# M837-pld-84.net
KiCad netlist of a schematic drawn in EAGLE
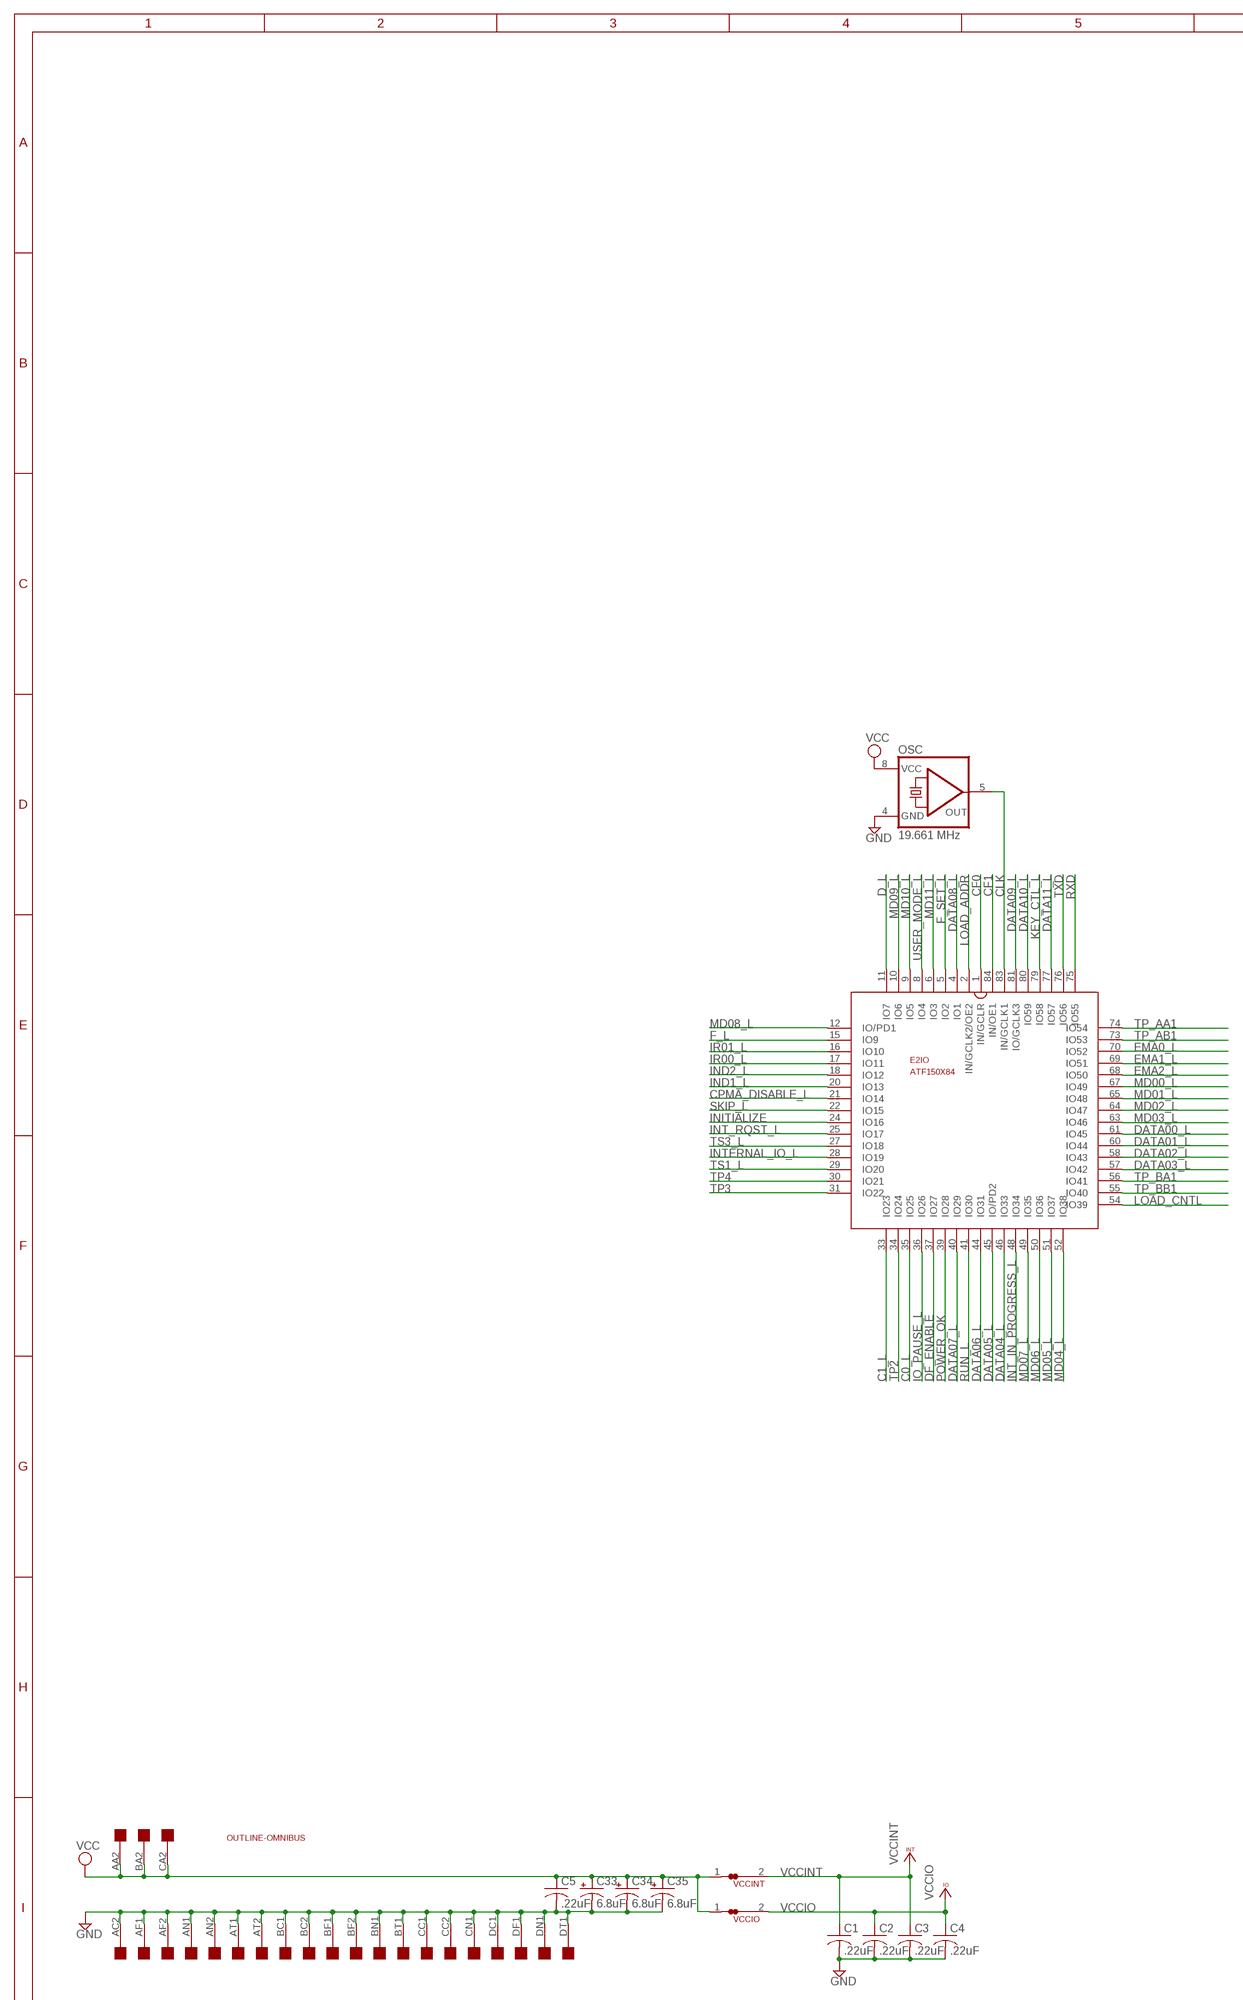
[diagram p0: schematic, sheet 1, part 1 of 2]
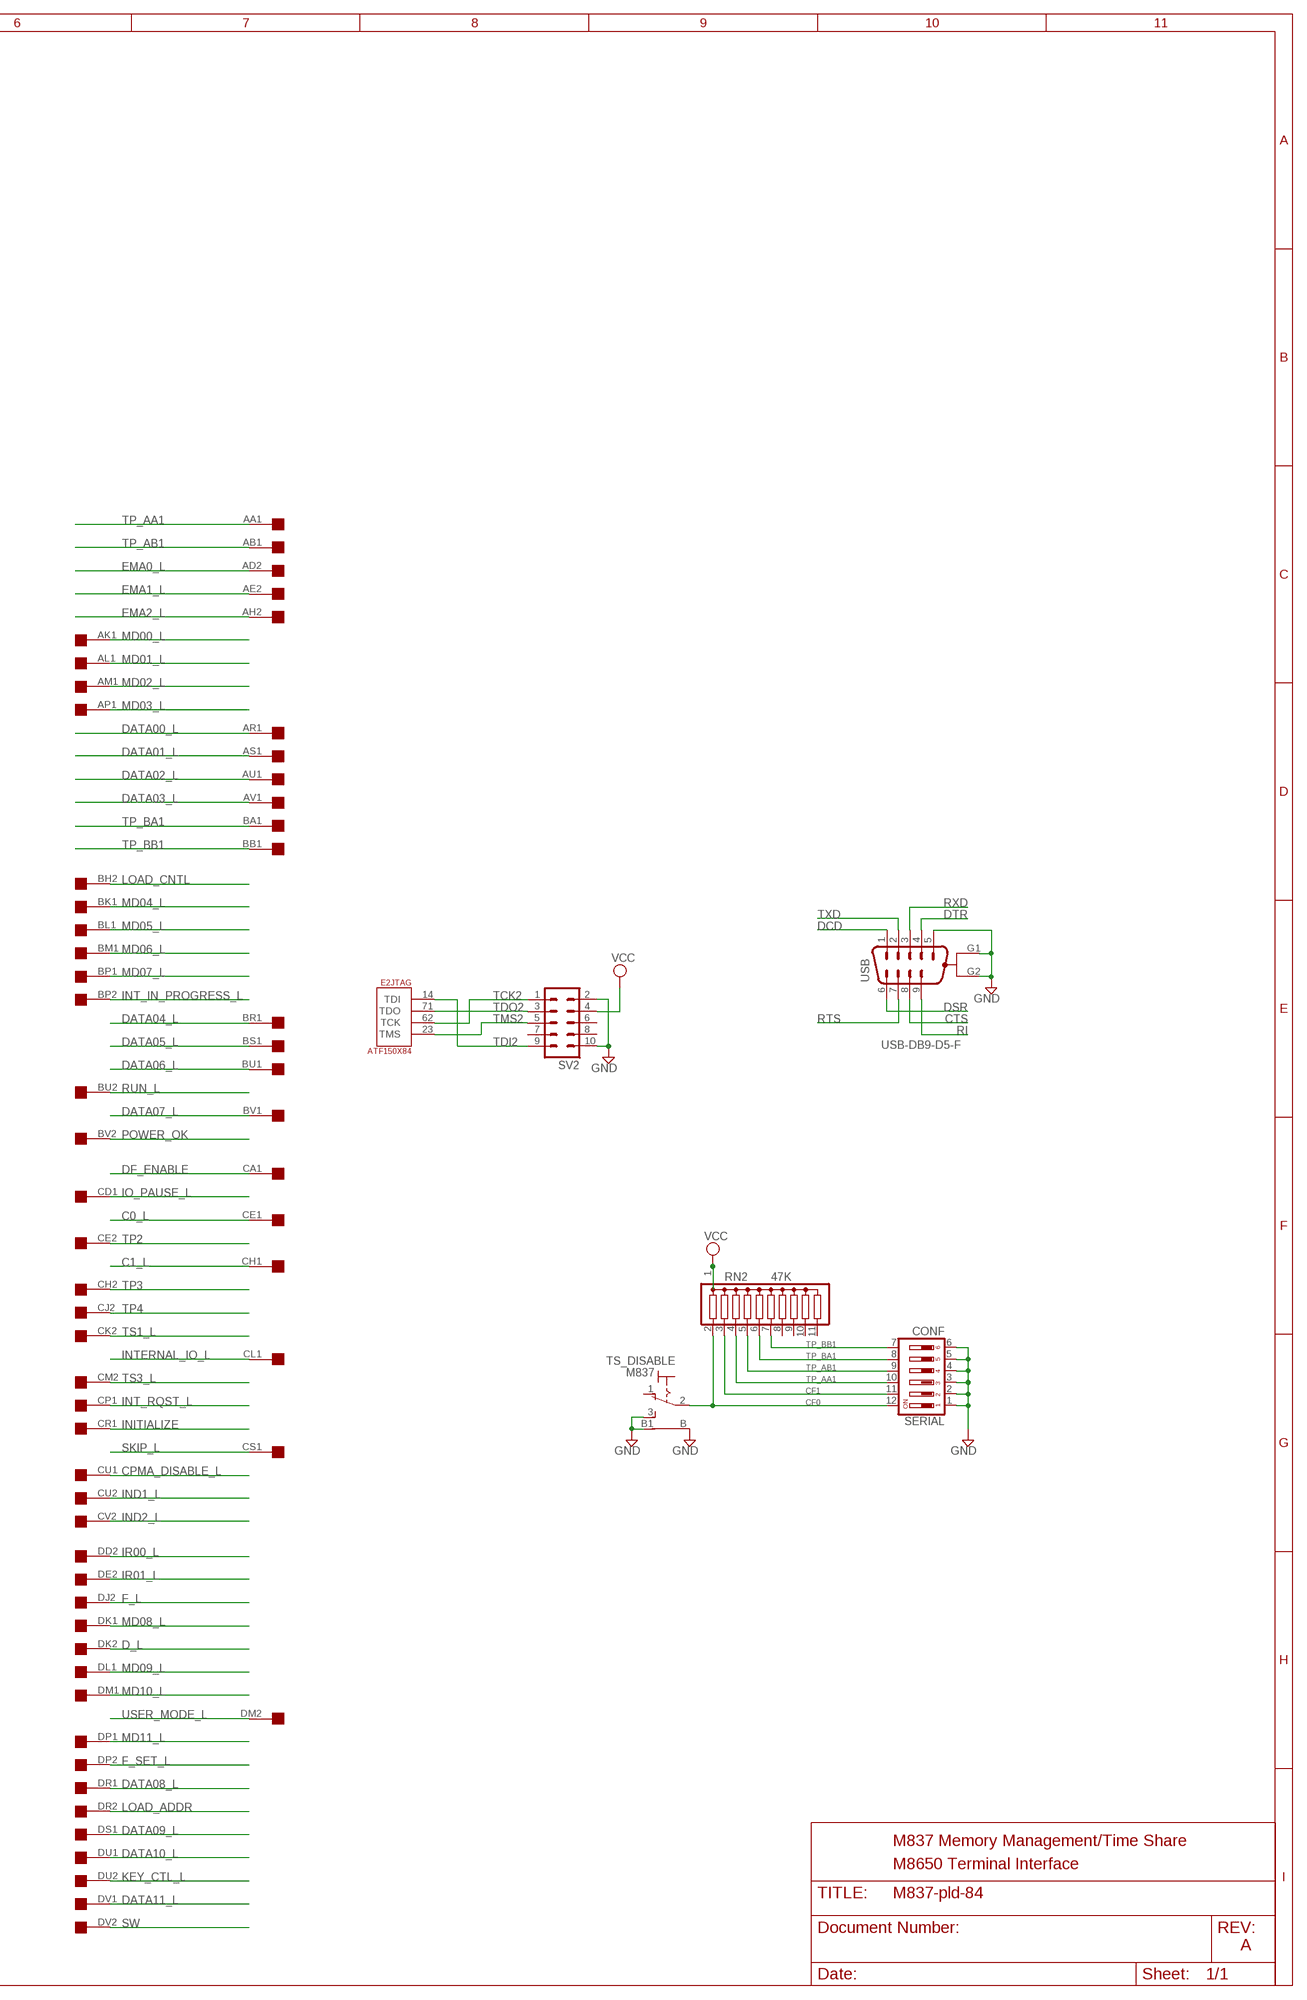
[diagram p1: schematic, sheet 1, part 2 of 2]

(export (version "E")
  (design (tool "Eeschema 10.0.6"))
  (components
    (comp (ref "C1")
      (value ".22uF")
      (footprint "eagle-import:C063-025X075")
      (libsource (lib "eagle-import") (part "C-US"))
    )
    (comp (ref "C2")
      (value ".22uF")
      (footprint "eagle-import:C063-025X075")
      (libsource (lib "eagle-import") (part "C-US"))
    )
    (comp (ref "C3")
      (value ".22uF")
      (footprint "eagle-import:C063-025X075")
      (libsource (lib "eagle-import") (part "C-US"))
    )
    (comp (ref "C4")
      (value ".22uF")
      (footprint "eagle-import:C063-025X075")
      (libsource (lib "eagle-import") (part "C-US"))
    )
    (comp (ref "C5")
      (value ".22uF")
      (footprint "eagle-import:C063-025X075")
      (libsource (lib "eagle-import") (part "C-US"))
    )
    (comp (ref "C33")
      (value "6.8uF")
      (footprint "eagle-import:E12-8")
      (libsource (lib "eagle-import") (part "CPOL-USE20-8AXIAL"))
    )
    (comp (ref "C34")
      (value "6.8uF")
      (footprint "eagle-import:E12-8")
      (libsource (lib "eagle-import") (part "CPOL-USE20-8AXIAL"))
    )
    (comp (ref "C35")
      (value "6.8uF")
      (footprint "eagle-import:E12-8")
      (libsource (lib "eagle-import") (part "CPOL-USE20-8AXIAL"))
    )
    (comp (ref "E2")
      (value "ATF150X84")
      (footprint "eagle-import:S84")
      (libsource (lib "eagle-import") (part "ATF150X84"))
    )
    (comp (ref "OSC")
      (value "19.661 MHz")
      (footprint "eagle-import:DIL08S")
      (libsource (lib "eagle-import") (part "QG5460"))
    )
    (comp (ref "RN2")
      (value "47K")
      (footprint "eagle-import:SIL11")
      (libsource (lib "eagle-import") (part "G10R"))
    )
    (comp (ref "SERIAL")
      (value "CONF")
      (footprint "eagle-import:DP-06")
      (fields (field (name "MPN") "MCDP06"))
      (libsource (lib "eagle-import") (part "DP06"))
    )
    (comp (ref "SV2")
      (value "ML10")
      (footprint "eagle-import:ML10")
      (libsource (lib "eagle-import") (part "ML10"))
    )
    (comp (ref "TS_DISABLE")
      (value "M837")
      (footprint "eagle-import:9070-1W")
      (libsource (lib "eagle-import") (part "9070-1W"))
    )
    (comp (ref "U$1")
      (value "QUAD")
      (footprint "eagle-import:EDGE-CON8")
      (libsource (lib "eagle-import") (part "QUAD"))
    )
    (comp (ref "U$2")
      (value "OUTLINE-OMNIBUS")
      (footprint "eagle-import:OMNIBUS")
      (libsource (lib "eagle-import") (part "OUTLINE-OMNIBUS"))
    )
    (comp (ref "USB")
      (value "USB-DB9-D5-F")
      (footprint "eagle-import:AMP_DB-9RA")
      (fields (field (name "MANF") "TE/AMP"))
      (libsource (lib "eagle-import") (part "DB9"))
    )
    (comp (ref "VCCINT")
      (value "JUMPER-NC1")
      (footprint "eagle-import:NC1")
      (libsource (lib "eagle-import") (part "JUMPER-NC1"))
    )
    (comp (ref "VCCIO")
      (value "JUMPER-NC1")
      (footprint "eagle-import:NC1")
      (libsource (lib "eagle-import") (part "JUMPER-NC1"))
    )
  )
  (nets
    (net (code "1") (name "/C0_L") (class "Default")
      (node (ref "E2") (pin "35") (pinfunction "IO25_35") (pintype "bidirectional"))
      (node (ref "U$1") (pin "CE1") (pinfunction "1_CE1") (pintype "bidirectional"))
    )
    (net (code "2") (name "/C1_L") (class "Default")
      (node (ref "E2") (pin "33") (pinfunction "IO23_33") (pintype "bidirectional"))
      (node (ref "U$1") (pin "CH1") (pinfunction "1_CH1") (pintype "bidirectional"))
    )
    (net (code "3") (name "/CF0") (class "Default")
      (node (ref "E2") (pin "1") (pinfunction "IN/GCLR_1") (pintype "input"))
      (node (ref "RN2") (pin "2") (pinfunction "2_2") (pintype "passive"))
      (node (ref "SERIAL") (pin "12") (pinfunction "12_12") (pintype "passive"))
      (node (ref "TS_DISABLE") (pin "2") (pinfunction "P_2") (pintype "passive"))
    )
    (net (code "4") (name "/CF1") (class "Default")
      (node (ref "E2") (pin "84") (pinfunction "IN/OE1_84") (pintype "input"))
      (node (ref "RN2") (pin "3") (pinfunction "3_3") (pintype "passive"))
      (node (ref "SERIAL") (pin "11") (pinfunction "11_11") (pintype "passive"))
    )
    (net (code "5") (name "/CLK") (class "Default")
      (node (ref "E2") (pin "83") (pinfunction "IN/GCLK1_83") (pintype "input"))
      (node (ref "OSC") (pin "5") (pinfunction "OUT_5") (pintype "output"))
    )
    (net (code "6") (name "/CPMA_DISABLE_L") (class "Default")
      (node (ref "E2") (pin "21") (pinfunction "IO14_21") (pintype "bidirectional"))
      (node (ref "U$1") (pin "CU1") (pinfunction "1_CU1") (pintype "bidirectional"))
    )
    (net (code "7") (name "/CTS") (class "Default")
      (node (ref "USB") (pin "8") (pinfunction "8_8") (pintype "passive"))
    )
    (net (code "8") (name "/DATA00_L") (class "Default")
      (node (ref "E2") (pin "61") (pinfunction "IO45_61") (pintype "bidirectional"))
      (node (ref "U$1") (pin "AR1") (pinfunction "1_AR1") (pintype "bidirectional"))
    )
    (net (code "9") (name "/DATA01_L") (class "Default")
      (node (ref "E2") (pin "60") (pinfunction "IO44_60") (pintype "bidirectional"))
      (node (ref "U$1") (pin "AS1") (pinfunction "1_AS1") (pintype "bidirectional"))
    )
    (net (code "10") (name "/DATA02_L") (class "Default")
      (node (ref "E2") (pin "58") (pinfunction "IO43_58") (pintype "bidirectional"))
      (node (ref "U$1") (pin "AU1") (pinfunction "1_AU1") (pintype "bidirectional"))
    )
    (net (code "11") (name "/DATA03_L") (class "Default")
      (node (ref "E2") (pin "57") (pinfunction "IO42_57") (pintype "bidirectional"))
      (node (ref "U$1") (pin "AV1") (pinfunction "1_AV1") (pintype "bidirectional"))
    )
    (net (code "12") (name "/DATA04_L") (class "Default")
      (node (ref "E2") (pin "46") (pinfunction "IO33_46") (pintype "bidirectional"))
      (node (ref "U$1") (pin "BR1") (pinfunction "1_BR1") (pintype "bidirectional"))
    )
    (net (code "13") (name "/DATA05_L") (class "Default")
      (node (ref "E2") (pin "45") (pinfunction "IO/PD2_45") (pintype "bidirectional"))
      (node (ref "U$1") (pin "BS1") (pinfunction "1_BS1") (pintype "bidirectional"))
    )
    (net (code "14") (name "/DATA06_L") (class "Default")
      (node (ref "E2") (pin "44") (pinfunction "IO31_44") (pintype "bidirectional"))
      (node (ref "U$1") (pin "BU1") (pinfunction "1_BU1") (pintype "bidirectional"))
    )
    (net (code "15") (name "/DATA07_L") (class "Default")
      (node (ref "E2") (pin "40") (pinfunction "IO29_40") (pintype "bidirectional"))
      (node (ref "U$1") (pin "BV1") (pinfunction "1_BV1") (pintype "bidirectional"))
    )
    (net (code "16") (name "/DATA08_L") (class "Default")
      (node (ref "E2") (pin "4") (pinfunction "IO1_4") (pintype "bidirectional"))
      (node (ref "U$1") (pin "DR1") (pinfunction "1_DR1") (pintype "bidirectional"))
    )
    (net (code "17") (name "/DATA09_L") (class "Default")
      (node (ref "E2") (pin "81") (pinfunction "IO/GCLK3_81") (pintype "bidirectional"))
      (node (ref "U$1") (pin "DS1") (pinfunction "1_DS1") (pintype "bidirectional"))
    )
    (net (code "18") (name "/DATA10_L") (class "Default")
      (node (ref "E2") (pin "80") (pinfunction "IO59_80") (pintype "bidirectional"))
      (node (ref "U$1") (pin "DU1") (pinfunction "1_DU1") (pintype "bidirectional"))
    )
    (net (code "19") (name "/DATA11_L") (class "Default")
      (node (ref "E2") (pin "77") (pinfunction "IO57_77") (pintype "bidirectional"))
      (node (ref "U$1") (pin "DV1") (pinfunction "1_DV1") (pintype "bidirectional"))
    )
    (net (code "20") (name "/DCD") (class "Default")
      (node (ref "USB") (pin "1") (pinfunction "1_1") (pintype "passive"))
    )
    (net (code "21") (name "/DF_ENABLE") (class "Default")
      (node (ref "E2") (pin "37") (pinfunction "IO27_37") (pintype "bidirectional"))
      (node (ref "U$1") (pin "CA1") (pinfunction "1_CA1") (pintype "bidirectional"))
    )
    (net (code "22") (name "/DSR") (class "Default")
      (node (ref "USB") (pin "6") (pinfunction "6_6") (pintype "passive"))
    )
    (net (code "23") (name "/DTR") (class "Default")
      (node (ref "USB") (pin "4") (pinfunction "4_4") (pintype "passive"))
    )
    (net (code "24") (name "/D_L") (class "Default")
      (node (ref "E2") (pin "11") (pinfunction "IO7_11") (pintype "bidirectional"))
      (node (ref "U$1") (pin "DK2") (pinfunction "1_DK2") (pintype "bidirectional"))
    )
    (net (code "25") (name "/EMA0_L") (class "Default")
      (node (ref "E2") (pin "70") (pinfunction "IO52_70") (pintype "bidirectional"))
      (node (ref "U$1") (pin "AD2") (pinfunction "1_AD2") (pintype "bidirectional"))
    )
    (net (code "26") (name "/EMA1_L") (class "Default")
      (node (ref "E2") (pin "69") (pinfunction "IO51_69") (pintype "bidirectional"))
      (node (ref "U$1") (pin "AE2") (pinfunction "1_AE2") (pintype "bidirectional"))
    )
    (net (code "27") (name "/EMA2_L") (class "Default")
      (node (ref "E2") (pin "68") (pinfunction "IO50_68") (pintype "bidirectional"))
      (node (ref "U$1") (pin "AH2") (pinfunction "1_AH2") (pintype "bidirectional"))
    )
    (net (code "28") (name "/F_L") (class "Default")
      (node (ref "E2") (pin "15") (pinfunction "IO9_15") (pintype "bidirectional"))
      (node (ref "U$1") (pin "DJ2") (pinfunction "1_DJ2") (pintype "bidirectional"))
    )
    (net (code "29") (name "/F_SET_L") (class "Default")
      (node (ref "E2") (pin "5") (pinfunction "IO2_5") (pintype "bidirectional"))
      (node (ref "U$1") (pin "DP2") (pinfunction "1_DP2") (pintype "bidirectional"))
    )
    (net (code "30") (name "/IND1_L") (class "Default")
      (node (ref "E2") (pin "20") (pinfunction "IO13_20") (pintype "bidirectional"))
      (node (ref "U$1") (pin "CU2") (pinfunction "1_CU2") (pintype "bidirectional"))
    )
    (net (code "31") (name "/IND2_L") (class "Default")
      (node (ref "E2") (pin "18") (pinfunction "IO12_18") (pintype "bidirectional"))
      (node (ref "U$1") (pin "CV2") (pinfunction "1_CV2") (pintype "bidirectional"))
    )
    (net (code "32") (name "/INITIALIZE") (class "Default")
      (node (ref "E2") (pin "24") (pinfunction "IO16_24") (pintype "bidirectional"))
      (node (ref "U$1") (pin "CR1") (pinfunction "1_CR1") (pintype "bidirectional"))
    )
    (net (code "33") (name "/INTERNAL_IO_L") (class "Default")
      (node (ref "E2") (pin "28") (pinfunction "IO19_28") (pintype "bidirectional"))
      (node (ref "U$1") (pin "CL1") (pinfunction "1_CL1") (pintype "bidirectional"))
    )
    (net (code "34") (name "/INT_IN_PROGRESS_L") (class "Default")
      (node (ref "E2") (pin "48") (pinfunction "IO34_48") (pintype "bidirectional"))
      (node (ref "U$1") (pin "BP2") (pinfunction "1_BP2") (pintype "bidirectional"))
    )
    (net (code "35") (name "/INT_RQST_L") (class "Default")
      (node (ref "E2") (pin "25") (pinfunction "IO17_25") (pintype "bidirectional"))
      (node (ref "U$1") (pin "CP1") (pinfunction "1_CP1") (pintype "bidirectional"))
    )
    (net (code "36") (name "/IO_PAUSE_L") (class "Default")
      (node (ref "E2") (pin "36") (pinfunction "IO26_36") (pintype "bidirectional"))
      (node (ref "U$1") (pin "CD1") (pinfunction "1_CD1") (pintype "bidirectional"))
    )
    (net (code "37") (name "/IR00_L") (class "Default")
      (node (ref "E2") (pin "17") (pinfunction "IO11_17") (pintype "bidirectional"))
      (node (ref "U$1") (pin "DD2") (pinfunction "1_DD2") (pintype "bidirectional"))
    )
    (net (code "38") (name "/IR01_L") (class "Default")
      (node (ref "E2") (pin "16") (pinfunction "IO10_16") (pintype "bidirectional"))
      (node (ref "U$1") (pin "DE2") (pinfunction "1_DE2") (pintype "bidirectional"))
    )
    (net (code "39") (name "/KEY_CTL_L") (class "Default")
      (node (ref "E2") (pin "79") (pinfunction "IO58_79") (pintype "bidirectional"))
      (node (ref "U$1") (pin "DU2") (pinfunction "1_DU2") (pintype "bidirectional"))
    )
    (net (code "40") (name "/LOAD_ADDR") (class "Default")
      (node (ref "E2") (pin "2") (pinfunction "IN/GCLK2/OE2_2") (pintype "input"))
      (node (ref "U$1") (pin "DR2") (pinfunction "1_DR2") (pintype "bidirectional"))
    )
    (net (code "41") (name "/LOAD_CNTL") (class "Default")
      (node (ref "E2") (pin "54") (pinfunction "IO39_54") (pintype "bidirectional"))
      (node (ref "U$1") (pin "BH2") (pinfunction "1_BH2") (pintype "bidirectional"))
    )
    (net (code "42") (name "/MD00_L") (class "Default")
      (node (ref "E2") (pin "67") (pinfunction "IO49_67") (pintype "bidirectional"))
      (node (ref "U$1") (pin "AK1") (pinfunction "1_AK1") (pintype "bidirectional"))
    )
    (net (code "43") (name "/MD01_L") (class "Default")
      (node (ref "E2") (pin "65") (pinfunction "IO48_65") (pintype "bidirectional"))
      (node (ref "U$1") (pin "AL1") (pinfunction "1_AL1") (pintype "bidirectional"))
    )
    (net (code "44") (name "/MD02_L") (class "Default")
      (node (ref "E2") (pin "64") (pinfunction "IO47_64") (pintype "bidirectional"))
      (node (ref "U$1") (pin "AM1") (pinfunction "1_AM1") (pintype "bidirectional"))
    )
    (net (code "45") (name "/MD03_L") (class "Default")
      (node (ref "E2") (pin "63") (pinfunction "IO46_63") (pintype "bidirectional"))
      (node (ref "U$1") (pin "AP1") (pinfunction "1_AP1") (pintype "bidirectional"))
    )
    (net (code "46") (name "/MD04_L") (class "Default")
      (node (ref "E2") (pin "52") (pinfunction "IO38_52") (pintype "bidirectional"))
      (node (ref "U$1") (pin "BK1") (pinfunction "1_BK1") (pintype "bidirectional"))
    )
    (net (code "47") (name "/MD05_L") (class "Default")
      (node (ref "E2") (pin "51") (pinfunction "IO37_51") (pintype "bidirectional"))
      (node (ref "U$1") (pin "BL1") (pinfunction "1_BL1") (pintype "bidirectional"))
    )
    (net (code "48") (name "/MD06_L") (class "Default")
      (node (ref "E2") (pin "50") (pinfunction "IO36_50") (pintype "bidirectional"))
      (node (ref "U$1") (pin "BM1") (pinfunction "1_BM1") (pintype "bidirectional"))
    )
    (net (code "49") (name "/MD07_L") (class "Default")
      (node (ref "E2") (pin "49") (pinfunction "IO35_49") (pintype "bidirectional"))
      (node (ref "U$1") (pin "BP1") (pinfunction "1_BP1") (pintype "bidirectional"))
    )
    (net (code "50") (name "/MD08_L") (class "Default")
      (node (ref "E2") (pin "12") (pinfunction "IO/PD1_12") (pintype "bidirectional"))
      (node (ref "U$1") (pin "DK1") (pinfunction "1_DK1") (pintype "bidirectional"))
    )
    (net (code "51") (name "/MD09_L") (class "Default")
      (node (ref "E2") (pin "10") (pinfunction "IO6_10") (pintype "bidirectional"))
      (node (ref "U$1") (pin "DL1") (pinfunction "1_DL1") (pintype "bidirectional"))
    )
    (net (code "52") (name "/MD10_L") (class "Default")
      (node (ref "E2") (pin "9") (pinfunction "IO5_9") (pintype "bidirectional"))
      (node (ref "U$1") (pin "DM1") (pinfunction "1_DM1") (pintype "bidirectional"))
    )
    (net (code "53") (name "/MD11_L") (class "Default")
      (node (ref "E2") (pin "6") (pinfunction "IO3_6") (pintype "bidirectional"))
      (node (ref "U$1") (pin "DP1") (pinfunction "1_DP1") (pintype "bidirectional"))
    )
    (net (code "54") (name "/POWER_OK") (class "Default")
      (node (ref "E2") (pin "39") (pinfunction "IO28_39") (pintype "bidirectional"))
      (node (ref "U$1") (pin "BV2") (pinfunction "1_BV2") (pintype "bidirectional"))
    )
    (net (code "55") (name "/RI") (class "Default")
      (node (ref "USB") (pin "9") (pinfunction "9_9") (pintype "passive"))
    )
    (net (code "56") (name "/RTS") (class "Default")
      (node (ref "USB") (pin "7") (pinfunction "7_7") (pintype "passive"))
    )
    (net (code "57") (name "/RUN_L") (class "Default")
      (node (ref "E2") (pin "41") (pinfunction "IO30_41") (pintype "bidirectional"))
      (node (ref "U$1") (pin "BU2") (pinfunction "1_BU2") (pintype "bidirectional"))
    )
    (net (code "58") (name "/RXD") (class "Default")
      (node (ref "E2") (pin "75") (pinfunction "IO55_75") (pintype "bidirectional"))
      (node (ref "USB") (pin "3") (pinfunction "3_3") (pintype "passive"))
    )
    (net (code "59") (name "/SKIP_L") (class "Default")
      (node (ref "E2") (pin "22") (pinfunction "IO15_22") (pintype "bidirectional"))
      (node (ref "U$1") (pin "CS1") (pinfunction "1_CS1") (pintype "bidirectional"))
    )
    (net (code "60") (name "/SW") (class "Default")
      (node (ref "U$1") (pin "DV2") (pinfunction "1_DV2") (pintype "bidirectional"))
    )
    (net (code "61") (name "/TCK2") (class "Default")
      (node (ref "E2") (pin "62") (pinfunction "TCK_62") (pintype "bidirectional"))
      (node (ref "SV2") (pin "1") (pinfunction "1_1") (pintype "passive"))
    )
    (net (code "62") (name "/TDI2") (class "Default")
      (node (ref "E2") (pin "14") (pinfunction "TDI_14") (pintype "bidirectional"))
      (node (ref "SV2") (pin "9") (pinfunction "9_9") (pintype "passive"))
    )
    (net (code "63") (name "/TDO2") (class "Default")
      (node (ref "E2") (pin "71") (pinfunction "TDO_71") (pintype "bidirectional"))
      (node (ref "SV2") (pin "3") (pinfunction "3_3") (pintype "passive"))
    )
    (net (code "64") (name "/TMS2") (class "Default")
      (node (ref "E2") (pin "23") (pinfunction "TMS_23") (pintype "bidirectional"))
      (node (ref "SV2") (pin "5") (pinfunction "5_5") (pintype "passive"))
    )
    (net (code "65") (name "/TP2") (class "Default")
      (node (ref "E2") (pin "34") (pinfunction "IO24_34") (pintype "bidirectional"))
      (node (ref "U$1") (pin "CE2") (pinfunction "1_CE2") (pintype "bidirectional"))
    )
    (net (code "66") (name "/TP3") (class "Default")
      (node (ref "E2") (pin "31") (pinfunction "IO22_31") (pintype "bidirectional"))
      (node (ref "U$1") (pin "CH2") (pinfunction "1_CH2") (pintype "bidirectional"))
    )
    (net (code "67") (name "/TP4") (class "Default")
      (node (ref "E2") (pin "30") (pinfunction "IO21_30") (pintype "bidirectional"))
      (node (ref "U$1") (pin "CJ2") (pinfunction "1_CJ2") (pintype "bidirectional"))
    )
    (net (code "68") (name "/TP_AA1") (class "Default")
      (node (ref "E2") (pin "74") (pinfunction "IO54_74") (pintype "bidirectional"))
      (node (ref "RN2") (pin "4") (pinfunction "4_4") (pintype "passive"))
      (node (ref "SERIAL") (pin "10") (pinfunction "10_10") (pintype "passive"))
      (node (ref "U$1") (pin "AA1") (pinfunction "1_AA1") (pintype "bidirectional"))
    )
    (net (code "69") (name "/TP_AB1") (class "Default")
      (node (ref "E2") (pin "73") (pinfunction "IO53_73") (pintype "bidirectional"))
      (node (ref "RN2") (pin "5") (pinfunction "5_5") (pintype "passive"))
      (node (ref "SERIAL") (pin "9") (pinfunction "9_9") (pintype "passive"))
      (node (ref "U$1") (pin "AB1") (pinfunction "1_AB1") (pintype "bidirectional"))
    )
    (net (code "70") (name "/TP_BA1") (class "Default")
      (node (ref "E2") (pin "56") (pinfunction "IO41_56") (pintype "bidirectional"))
      (node (ref "RN2") (pin "6") (pinfunction "6_6") (pintype "passive"))
      (node (ref "SERIAL") (pin "8") (pinfunction "8_8") (pintype "passive"))
      (node (ref "U$1") (pin "BA1") (pinfunction "1_BA1") (pintype "bidirectional"))
    )
    (net (code "71") (name "/TP_BB1") (class "Default")
      (node (ref "E2") (pin "55") (pinfunction "IO40_55") (pintype "bidirectional"))
      (node (ref "RN2") (pin "7") (pinfunction "7_7") (pintype "passive"))
      (node (ref "SERIAL") (pin "7") (pinfunction "7_7") (pintype "passive"))
      (node (ref "U$1") (pin "BB1") (pinfunction "1_BB1") (pintype "bidirectional"))
    )
    (net (code "72") (name "/TS1_L") (class "Default")
      (node (ref "E2") (pin "29") (pinfunction "IO20_29") (pintype "bidirectional"))
      (node (ref "U$1") (pin "CK2") (pinfunction "1_CK2") (pintype "bidirectional"))
    )
    (net (code "73") (name "/TS3_L") (class "Default")
      (node (ref "E2") (pin "27") (pinfunction "IO18_27") (pintype "bidirectional"))
      (node (ref "U$1") (pin "CM2") (pinfunction "1_CM2") (pintype "bidirectional"))
    )
    (net (code "74") (name "/TXD") (class "Default")
      (node (ref "E2") (pin "76") (pinfunction "IO56_76") (pintype "bidirectional"))
      (node (ref "USB") (pin "2") (pinfunction "2_2") (pintype "passive"))
    )
    (net (code "75") (name "/USER_MODE_L") (class "Default")
      (node (ref "E2") (pin "8") (pinfunction "IO4_8") (pintype "bidirectional"))
      (node (ref "U$1") (pin "DM2") (pinfunction "1_DM2") (pintype "bidirectional"))
    )
    (net (code "76") (name "GND") (class "Default")
      (node (ref "C1") (pin "2") (pinfunction "2_2") (pintype "passive"))
      (node (ref "C2") (pin "2") (pinfunction "2_2") (pintype "passive"))
      (node (ref "C3") (pin "2") (pinfunction "2_2") (pintype "passive"))
      (node (ref "C33") (pin "-") (pinfunction "-_-") (pintype "passive"))
      (node (ref "C34") (pin "-") (pinfunction "-_-") (pintype "passive"))
      (node (ref "C35") (pin "-") (pinfunction "-_-") (pintype "passive"))
      (node (ref "C4") (pin "2") (pinfunction "2_2") (pintype "passive"))
      (node (ref "C5") (pin "2") (pinfunction "2_2") (pintype "passive"))
      (node (ref "OSC") (pin "4") (pinfunction "GND_4") (pintype "power_in"))
      (node (ref "SERIAL") (pin "1") (pinfunction "1_1") (pintype "passive"))
      (node (ref "SERIAL") (pin "2") (pinfunction "2_2") (pintype "passive"))
      (node (ref "SERIAL") (pin "3") (pinfunction "3_3") (pintype "passive"))
      (node (ref "SERIAL") (pin "4") (pinfunction "4_4") (pintype "passive"))
      (node (ref "SERIAL") (pin "5") (pinfunction "5_5") (pintype "passive"))
      (node (ref "SERIAL") (pin "6") (pinfunction "6_6") (pintype "passive"))
      (node (ref "SV2") (pin "10") (pinfunction "10_10") (pintype "passive"))
      (node (ref "SV2") (pin "2") (pinfunction "2_2") (pintype "passive"))
      (node (ref "TS_DISABLE") (pin "3") (pinfunction "S_3") (pintype "passive"))
      (node (ref "TS_DISABLE") (pin "B") (pinfunction "B_B") (pintype "passive"))
      (node (ref "TS_DISABLE") (pin "B1") (pinfunction "B1_B1") (pintype "passive"))
      (node (ref "U$1") (pin "AC2") (pinfunction "1_AC2") (pintype "bidirectional"))
      (node (ref "U$1") (pin "AF1") (pinfunction "1_AF1") (pintype "bidirectional"))
      (node (ref "U$1") (pin "AF2") (pinfunction "1_AF2") (pintype "bidirectional"))
      (node (ref "U$1") (pin "AN1") (pinfunction "1_AN1") (pintype "bidirectional"))
      (node (ref "U$1") (pin "AN2") (pinfunction "1_AN2") (pintype "bidirectional"))
      (node (ref "U$1") (pin "AT1") (pinfunction "1_AT1") (pintype "bidirectional"))
      (node (ref "U$1") (pin "AT2") (pinfunction "1_AT2") (pintype "bidirectional"))
      (node (ref "U$1") (pin "BC1") (pinfunction "1_BC1") (pintype "bidirectional"))
      (node (ref "U$1") (pin "BC2") (pinfunction "1_BC2") (pintype "bidirectional"))
      (node (ref "U$1") (pin "BF1") (pinfunction "1_BF1") (pintype "bidirectional"))
      (node (ref "U$1") (pin "BF2") (pinfunction "1_BF2") (pintype "bidirectional"))
      (node (ref "U$1") (pin "BN1") (pinfunction "1_BN1") (pintype "bidirectional"))
      (node (ref "U$1") (pin "BT1") (pinfunction "1_BT1") (pintype "bidirectional"))
      (node (ref "U$1") (pin "CC1") (pinfunction "1_CC1") (pintype "bidirectional"))
      (node (ref "U$1") (pin "CC2") (pinfunction "1_CC2") (pintype "bidirectional"))
      (node (ref "U$1") (pin "CN1") (pinfunction "1_CN1") (pintype "bidirectional"))
      (node (ref "U$1") (pin "DC1") (pinfunction "1_DC1") (pintype "bidirectional"))
      (node (ref "U$1") (pin "DF1") (pinfunction "1_DF1") (pintype "bidirectional"))
      (node (ref "U$1") (pin "DN1") (pinfunction "1_DN1") (pintype "bidirectional"))
      (node (ref "U$1") (pin "DT1") (pinfunction "1_DT1") (pintype "bidirectional"))
      (node (ref "USB") (pin "5") (pinfunction "5_5") (pintype "passive"))
      (node (ref "USB") (pin "G1") (pinfunction "G1_G1") (pintype "passive"))
      (node (ref "USB") (pin "G2") (pinfunction "G2_G2") (pintype "passive"))
    )
    (net (code "77") (name "VCC") (class "Default")
      (node (ref "C33") (pin "+") (pinfunction "+_+") (pintype "passive"))
      (node (ref "C34") (pin "+") (pinfunction "+_+") (pintype "passive"))
      (node (ref "C35") (pin "+") (pinfunction "+_+") (pintype "passive"))
      (node (ref "C5") (pin "1") (pinfunction "1_1") (pintype "passive"))
      (node (ref "OSC") (pin "8") (pinfunction "VCC_8") (pintype "power_in"))
      (node (ref "RN2") (pin "1") (pinfunction "1_1") (pintype "passive"))
      (node (ref "SV2") (pin "4") (pinfunction "4_4") (pintype "passive"))
      (node (ref "U$1") (pin "AA2") (pinfunction "1_AA2") (pintype "bidirectional"))
      (node (ref "U$1") (pin "BA2") (pinfunction "1_BA2") (pintype "bidirectional"))
      (node (ref "U$1") (pin "CA2") (pinfunction "1_CA2") (pintype "bidirectional"))
      (node (ref "VCCINT") (pin "1") (pinfunction "1_1") (pintype "bidirectional"))
      (node (ref "VCCIO") (pin "1") (pinfunction "1_1") (pintype "bidirectional"))
    )
    (net (code "78") (name "VCCINT") (class "Default")
      (node (ref "C1") (pin "1") (pinfunction "1_1") (pintype "passive"))
      (node (ref "C3") (pin "1") (pinfunction "1_1") (pintype "passive"))
      (node (ref "VCCINT") (pin "2") (pinfunction "2_2") (pintype "bidirectional"))
    )
    (net (code "79") (name "VCCIO") (class "Default")
      (node (ref "C2") (pin "1") (pinfunction "1_1") (pintype "passive"))
      (node (ref "C4") (pin "1") (pinfunction "1_1") (pintype "passive"))
      (node (ref "VCCIO") (pin "2") (pinfunction "2_2") (pintype "bidirectional"))
    )
    (net (code "80") (name "unconnected-(RN2-Pad8)") (class "Default")
      (node (ref "RN2") (pin "8") (pinfunction "8_8") (pintype "passive"))
    )
    (net (code "81") (name "unconnected-(RN2-Pad9)") (class "Default")
      (node (ref "RN2") (pin "9") (pinfunction "9_9") (pintype "passive"))
    )
    (net (code "82") (name "unconnected-(RN2-Pad10)") (class "Default")
      (node (ref "RN2") (pin "10") (pinfunction "10_10") (pintype "passive"))
    )
    (net (code "83") (name "unconnected-(RN2-Pad11)") (class "Default")
      (node (ref "RN2") (pin "11") (pinfunction "11_11") (pintype "passive"))
    )
    (net (code "84") (name "unconnected-(SV2-Pad6)") (class "Default")
      (node (ref "SV2") (pin "6") (pinfunction "6_6") (pintype "passive"))
    )
    (net (code "85") (name "unconnected-(SV2-Pad7)") (class "Default")
      (node (ref "SV2") (pin "7") (pinfunction "7_7") (pintype "passive"))
    )
    (net (code "86") (name "unconnected-(SV2-Pad8)") (class "Default")
      (node (ref "SV2") (pin "8") (pinfunction "8_8") (pintype "passive"))
    )
    (net (code "87") (name "unconnected-(TS_DISABLE-O-Pad1)") (class "Default")
      (node (ref "TS_DISABLE") (pin "1") (pinfunction "O_1") (pintype "passive"))
    )
  )
)
